# CET-124-120W.net
KiCad netlist of a schematic drawn in Altium Designer
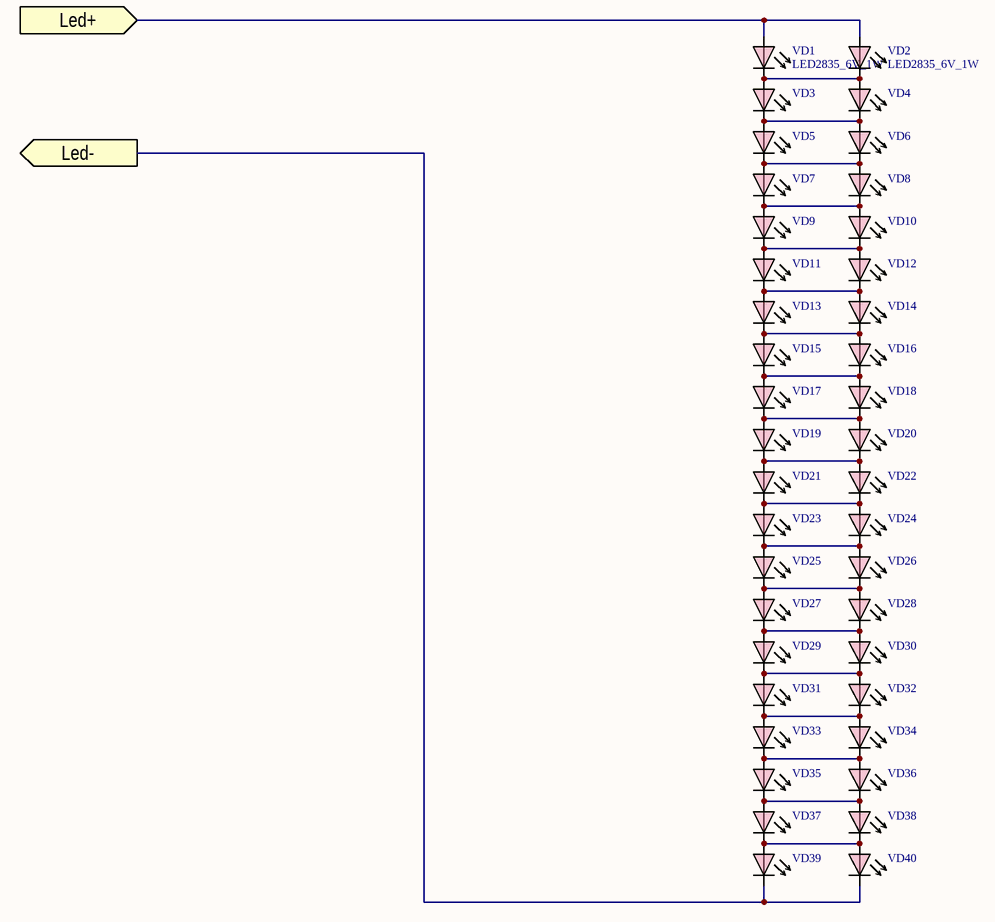
[diagram p0: CET-124-120W.SchDoc]

(export (version "E")
  (design (tool "Eeschema 10.0.6"))
  (components
    (comp (ref "VD1") (value "LED2835_6V_1W") (footprint "2835") (libsource (lib "Диоды") (part "Светодиод")))
    (comp (ref "VD2") (value "LED2835_6V_1W") (footprint "2835") (libsource (lib "Диоды") (part "Светодиод")))
    (comp (ref "VD3") (value "LED2835_6V_1W") (footprint "2835") (libsource (lib "Диоды") (part "Светодиод")))
    (comp (ref "VD4") (value "LED2835_6V_1W") (footprint "2835") (libsource (lib "Диоды") (part "Светодиод")))
    (comp (ref "VD5") (value "LED2835_6V_1W") (footprint "2835") (libsource (lib "Диоды") (part "Светодиод")))
    (comp (ref "VD6") (value "LED2835_6V_1W") (footprint "2835") (libsource (lib "Диоды") (part "Светодиод")))
    (comp (ref "VD7") (value "LED2835_6V_1W") (footprint "2835") (libsource (lib "Диоды") (part "Светодиод")))
    (comp (ref "VD8") (value "LED2835_6V_1W") (footprint "2835") (libsource (lib "Диоды") (part "Светодиод")))
    (comp (ref "VD9") (value "LED2835_6V_1W") (footprint "2835") (libsource (lib "Диоды") (part "Светодиод")))
    (comp (ref "VD10")
      (value "LED2835_6V_1W")
      (footprint "2835")
      (libsource (lib "Диоды") (part "Светодиод"))
    )
    (comp (ref "VD11")
      (value "LED2835_6V_1W")
      (footprint "2835")
      (libsource (lib "Диоды") (part "Светодиод"))
    )
    (comp (ref "VD12")
      (value "LED2835_6V_1W")
      (footprint "2835")
      (libsource (lib "Диоды") (part "Светодиод"))
    )
    (comp (ref "VD13")
      (value "LED2835_6V_1W")
      (footprint "2835")
      (libsource (lib "Диоды") (part "Светодиод"))
    )
    (comp (ref "VD14")
      (value "LED2835_6V_1W")
      (footprint "2835")
      (libsource (lib "Диоды") (part "Светодиод"))
    )
    (comp (ref "VD15")
      (value "LED2835_6V_1W")
      (footprint "2835")
      (libsource (lib "Диоды") (part "Светодиод"))
    )
    (comp (ref "VD16")
      (value "LED2835_6V_1W")
      (footprint "2835")
      (libsource (lib "Диоды") (part "Светодиод"))
    )
    (comp (ref "VD17")
      (value "LED2835_6V_1W")
      (footprint "2835")
      (libsource (lib "Диоды") (part "Светодиод"))
    )
    (comp (ref "VD18")
      (value "LED2835_6V_1W")
      (footprint "2835")
      (libsource (lib "Диоды") (part "Светодиод"))
    )
    (comp (ref "VD19")
      (value "LED2835_6V_1W")
      (footprint "2835")
      (libsource (lib "Диоды") (part "Светодиод"))
    )
    (comp (ref "VD20")
      (value "LED2835_6V_1W")
      (footprint "2835")
      (libsource (lib "Диоды") (part "Светодиод"))
    )
    (comp (ref "VD21")
      (value "LED2835_6V_1W")
      (footprint "2835")
      (libsource (lib "Диоды") (part "Светодиод"))
    )
    (comp (ref "VD22")
      (value "LED2835_6V_1W")
      (footprint "2835")
      (libsource (lib "Диоды") (part "Светодиод"))
    )
    (comp (ref "VD23")
      (value "LED2835_6V_1W")
      (footprint "2835")
      (libsource (lib "Диоды") (part "Светодиод"))
    )
    (comp (ref "VD24")
      (value "LED2835_6V_1W")
      (footprint "2835")
      (libsource (lib "Диоды") (part "Светодиод"))
    )
    (comp (ref "VD25")
      (value "LED2835_6V_1W")
      (footprint "2835")
      (libsource (lib "Диоды") (part "Светодиод"))
    )
    (comp (ref "VD26")
      (value "LED2835_6V_1W")
      (footprint "2835")
      (libsource (lib "Диоды") (part "Светодиод"))
    )
    (comp (ref "VD27")
      (value "LED2835_6V_1W")
      (footprint "2835")
      (libsource (lib "Диоды") (part "Светодиод"))
    )
    (comp (ref "VD28")
      (value "LED2835_6V_1W")
      (footprint "2835")
      (libsource (lib "Диоды") (part "Светодиод"))
    )
    (comp (ref "VD29")
      (value "LED2835_6V_1W")
      (footprint "2835")
      (libsource (lib "Диоды") (part "Светодиод"))
    )
    (comp (ref "VD30")
      (value "LED2835_6V_1W")
      (footprint "2835")
      (libsource (lib "Диоды") (part "Светодиод"))
    )
    (comp (ref "VD31")
      (value "LED2835_6V_1W")
      (footprint "2835")
      (libsource (lib "Диоды") (part "Светодиод"))
    )
    (comp (ref "VD32")
      (value "LED2835_6V_1W")
      (footprint "2835")
      (libsource (lib "Диоды") (part "Светодиод"))
    )
    (comp (ref "VD33")
      (value "LED2835_6V_1W")
      (footprint "2835")
      (libsource (lib "Диоды") (part "Светодиод"))
    )
    (comp (ref "VD34")
      (value "LED2835_6V_1W")
      (footprint "2835")
      (libsource (lib "Диоды") (part "Светодиод"))
    )
    (comp (ref "VD35")
      (value "LED2835_6V_1W")
      (footprint "2835")
      (libsource (lib "Диоды") (part "Светодиод"))
    )
    (comp (ref "VD36")
      (value "LED2835_6V_1W")
      (footprint "2835")
      (libsource (lib "Диоды") (part "Светодиод"))
    )
    (comp (ref "VD37")
      (value "LED2835_6V_1W")
      (footprint "2835")
      (libsource (lib "Диоды") (part "Светодиод"))
    )
    (comp (ref "VD38")
      (value "LED2835_6V_1W")
      (footprint "2835")
      (libsource (lib "Диоды") (part "Светодиод"))
    )
    (comp (ref "VD39")
      (value "LED2835_6V_1W")
      (footprint "2835")
      (libsource (lib "Диоды") (part "Светодиод"))
    )
    (comp (ref "VD40")
      (value "LED2835_6V_1W")
      (footprint "2835")
      (libsource (lib "Диоды") (part "Светодиод"))
    )
  )
  (nets
    (net (code "1") (name "/Led+") (class "Default")
      (node (ref "VD1") (pin "1") (pinfunction "A_1") (pintype "passive"))
      (node (ref "VD2") (pin "1") (pinfunction "A_1") (pintype "passive"))
    )
    (net (code "2") (name "/Led-") (class "Default")
      (node (ref "VD39") (pin "2") (pinfunction "C_2") (pintype "passive"))
      (node (ref "VD40") (pin "2") (pinfunction "C_2") (pintype "passive"))
    )
    (net (code "3") (name "Net-(VD1-C)") (class "Default")
      (node (ref "VD1") (pin "2") (pinfunction "C_2") (pintype "passive"))
      (node (ref "VD2") (pin "2") (pinfunction "C_2") (pintype "passive"))
      (node (ref "VD3") (pin "1") (pinfunction "A_1") (pintype "passive"))
      (node (ref "VD4") (pin "1") (pinfunction "A_1") (pintype "passive"))
    )
    (net (code "4") (name "Net-(VD3-C)") (class "Default")
      (node (ref "VD3") (pin "2") (pinfunction "C_2") (pintype "passive"))
      (node (ref "VD4") (pin "2") (pinfunction "C_2") (pintype "passive"))
      (node (ref "VD5") (pin "1") (pinfunction "A_1") (pintype "passive"))
      (node (ref "VD6") (pin "1") (pinfunction "A_1") (pintype "passive"))
    )
    (net (code "5") (name "Net-(VD5-C)") (class "Default")
      (node (ref "VD5") (pin "2") (pinfunction "C_2") (pintype "passive"))
      (node (ref "VD6") (pin "2") (pinfunction "C_2") (pintype "passive"))
      (node (ref "VD7") (pin "1") (pinfunction "A_1") (pintype "passive"))
      (node (ref "VD8") (pin "1") (pinfunction "A_1") (pintype "passive"))
    )
    (net (code "6") (name "Net-(VD10-A)") (class "Default")
      (node (ref "VD10") (pin "1") (pinfunction "A_1") (pintype "passive"))
      (node (ref "VD7") (pin "2") (pinfunction "C_2") (pintype "passive"))
      (node (ref "VD8") (pin "2") (pinfunction "C_2") (pintype "passive"))
      (node (ref "VD9") (pin "1") (pinfunction "A_1") (pintype "passive"))
    )
    (net (code "7") (name "Net-(VD10-C)") (class "Default")
      (node (ref "VD10") (pin "2") (pinfunction "C_2") (pintype "passive"))
      (node (ref "VD11") (pin "1") (pinfunction "A_1") (pintype "passive"))
      (node (ref "VD12") (pin "1") (pinfunction "A_1") (pintype "passive"))
      (node (ref "VD9") (pin "2") (pinfunction "C_2") (pintype "passive"))
    )
    (net (code "8") (name "Net-(VD11-C)") (class "Default")
      (node (ref "VD11") (pin "2") (pinfunction "C_2") (pintype "passive"))
      (node (ref "VD12") (pin "2") (pinfunction "C_2") (pintype "passive"))
      (node (ref "VD13") (pin "1") (pinfunction "A_1") (pintype "passive"))
      (node (ref "VD14") (pin "1") (pinfunction "A_1") (pintype "passive"))
    )
    (net (code "9") (name "Net-(VD13-C)") (class "Default")
      (node (ref "VD13") (pin "2") (pinfunction "C_2") (pintype "passive"))
      (node (ref "VD14") (pin "2") (pinfunction "C_2") (pintype "passive"))
      (node (ref "VD15") (pin "1") (pinfunction "A_1") (pintype "passive"))
      (node (ref "VD16") (pin "1") (pinfunction "A_1") (pintype "passive"))
    )
    (net (code "10") (name "Net-(VD15-C)") (class "Default")
      (node (ref "VD15") (pin "2") (pinfunction "C_2") (pintype "passive"))
      (node (ref "VD16") (pin "2") (pinfunction "C_2") (pintype "passive"))
      (node (ref "VD17") (pin "1") (pinfunction "A_1") (pintype "passive"))
      (node (ref "VD18") (pin "1") (pinfunction "A_1") (pintype "passive"))
    )
    (net (code "11") (name "Net-(VD17-C)") (class "Default")
      (node (ref "VD17") (pin "2") (pinfunction "C_2") (pintype "passive"))
      (node (ref "VD18") (pin "2") (pinfunction "C_2") (pintype "passive"))
      (node (ref "VD19") (pin "1") (pinfunction "A_1") (pintype "passive"))
      (node (ref "VD20") (pin "1") (pinfunction "A_1") (pintype "passive"))
    )
    (net (code "12") (name "Net-(VD19-C)") (class "Default")
      (node (ref "VD19") (pin "2") (pinfunction "C_2") (pintype "passive"))
      (node (ref "VD20") (pin "2") (pinfunction "C_2") (pintype "passive"))
      (node (ref "VD21") (pin "1") (pinfunction "A_1") (pintype "passive"))
      (node (ref "VD22") (pin "1") (pinfunction "A_1") (pintype "passive"))
    )
    (net (code "13") (name "Net-(VD21-C)") (class "Default")
      (node (ref "VD21") (pin "2") (pinfunction "C_2") (pintype "passive"))
      (node (ref "VD22") (pin "2") (pinfunction "C_2") (pintype "passive"))
      (node (ref "VD23") (pin "1") (pinfunction "A_1") (pintype "passive"))
      (node (ref "VD24") (pin "1") (pinfunction "A_1") (pintype "passive"))
    )
    (net (code "14") (name "Net-(VD23-C)") (class "Default")
      (node (ref "VD23") (pin "2") (pinfunction "C_2") (pintype "passive"))
      (node (ref "VD24") (pin "2") (pinfunction "C_2") (pintype "passive"))
      (node (ref "VD25") (pin "1") (pinfunction "A_1") (pintype "passive"))
      (node (ref "VD26") (pin "1") (pinfunction "A_1") (pintype "passive"))
    )
    (net (code "15") (name "Net-(VD25-C)") (class "Default")
      (node (ref "VD25") (pin "2") (pinfunction "C_2") (pintype "passive"))
      (node (ref "VD26") (pin "2") (pinfunction "C_2") (pintype "passive"))
      (node (ref "VD27") (pin "1") (pinfunction "A_1") (pintype "passive"))
      (node (ref "VD28") (pin "1") (pinfunction "A_1") (pintype "passive"))
    )
    (net (code "16") (name "Net-(VD27-C)") (class "Default")
      (node (ref "VD27") (pin "2") (pinfunction "C_2") (pintype "passive"))
      (node (ref "VD28") (pin "2") (pinfunction "C_2") (pintype "passive"))
      (node (ref "VD29") (pin "1") (pinfunction "A_1") (pintype "passive"))
      (node (ref "VD30") (pin "1") (pinfunction "A_1") (pintype "passive"))
    )
    (net (code "17") (name "Net-(VD29-C)") (class "Default")
      (node (ref "VD29") (pin "2") (pinfunction "C_2") (pintype "passive"))
      (node (ref "VD30") (pin "2") (pinfunction "C_2") (pintype "passive"))
      (node (ref "VD31") (pin "1") (pinfunction "A_1") (pintype "passive"))
      (node (ref "VD32") (pin "1") (pinfunction "A_1") (pintype "passive"))
    )
    (net (code "18") (name "Net-(VD31-C)") (class "Default")
      (node (ref "VD31") (pin "2") (pinfunction "C_2") (pintype "passive"))
      (node (ref "VD32") (pin "2") (pinfunction "C_2") (pintype "passive"))
      (node (ref "VD33") (pin "1") (pinfunction "A_1") (pintype "passive"))
      (node (ref "VD34") (pin "1") (pinfunction "A_1") (pintype "passive"))
    )
    (net (code "19") (name "Net-(VD33-C)") (class "Default")
      (node (ref "VD33") (pin "2") (pinfunction "C_2") (pintype "passive"))
      (node (ref "VD34") (pin "2") (pinfunction "C_2") (pintype "passive"))
      (node (ref "VD35") (pin "1") (pinfunction "A_1") (pintype "passive"))
      (node (ref "VD36") (pin "1") (pinfunction "A_1") (pintype "passive"))
    )
    (net (code "20") (name "Net-(VD35-C)") (class "Default")
      (node (ref "VD35") (pin "2") (pinfunction "C_2") (pintype "passive"))
      (node (ref "VD36") (pin "2") (pinfunction "C_2") (pintype "passive"))
      (node (ref "VD37") (pin "1") (pinfunction "A_1") (pintype "passive"))
      (node (ref "VD38") (pin "1") (pinfunction "A_1") (pintype "passive"))
    )
    (net (code "21") (name "Net-(VD37-C)") (class "Default")
      (node (ref "VD37") (pin "2") (pinfunction "C_2") (pintype "passive"))
      (node (ref "VD38") (pin "2") (pinfunction "C_2") (pintype "passive"))
      (node (ref "VD39") (pin "1") (pinfunction "A_1") (pintype "passive"))
      (node (ref "VD40") (pin "1") (pinfunction "A_1") (pintype "passive"))
    )
  )
)
